# CircuitoEMitter.net
KiCad netlist of a schematic drawn in EAGLE
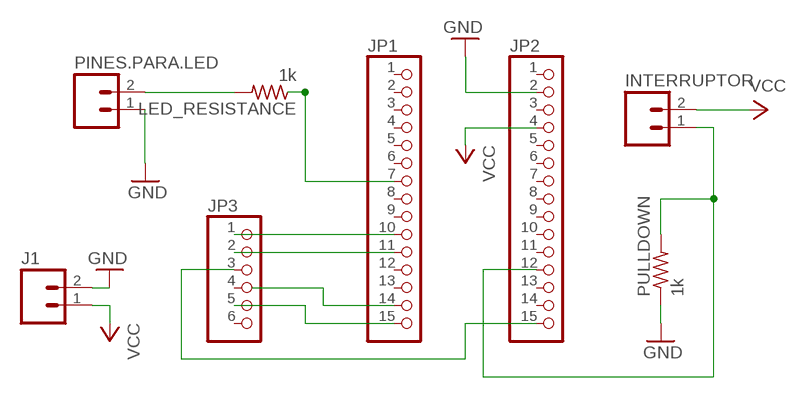
[diagram p0: schematic, sheet 1]

(export (version "E")
  (design (tool "Eeschema 10.0.6"))
  (components
    (comp (ref "INTERRUPTOR")
      (value "M02LOCK_LONGPADS")
      (footprint "eagle-import:1X02_LOCK_LONGPADS")
      (libsource (lib "eagle-import") (part "M02LOCK_LONGPADS"))
    )
    (comp (ref "J1")
      (value "M02POGO_PIN_HOLES_ONLY")
      (footprint "eagle-import:1X02_PP_HOLES_ONLY")
      (libsource (lib "eagle-import") (part "M02POGO_PIN_HOLES_ONLY"))
    )
    (comp (ref "JP1")
      (value "PINHD-1X15-CB")
      (footprint "eagle-import:1X15-CB")
      (libsource (lib "eagle-import") (part "PINHD-1X15-CB"))
    )
    (comp (ref "JP2")
      (value "PINHD-1X15-CB")
      (footprint "eagle-import:1X15-CB")
      (libsource (lib "eagle-import") (part "PINHD-1X15-CB"))
    )
    (comp (ref "JP3")
      (value "PINHD-1X6CLEAN")
      (footprint "eagle-import:1X06-CLEAN")
      (libsource (lib "eagle-import") (part "PINHD-1X6CLEAN"))
    )
    (comp (ref "LED_RESISTANCE")
      (value "1k")
      (footprint "eagle-import:0204_7")
      (libsource (lib "eagle-import") (part "R-US_0204/7"))
    )
    (comp (ref "PINES.PARA.LED")
      (value "M02LOCK_LONGPADS")
      (footprint "eagle-import:1X02_LOCK_LONGPADS")
      (libsource (lib "eagle-import") (part "M02LOCK_LONGPADS"))
    )
    (comp (ref "PULLDOWN")
      (value "1k")
      (footprint "eagle-import:0204_7")
      (libsource (lib "eagle-import") (part "R-US_0204/7"))
    )
  )
  (nets
    (net (code "1") (name "GND") (class "Default")
      (node (ref "J1") (pin "2") (pinfunction "2_2") (pintype "passive"))
      (node (ref "JP2") (pin "2") (pinfunction "2_2") (pintype "passive"))
      (node (ref "PINES.PARA.LED") (pin "1") (pinfunction "1_1") (pintype "passive"))
      (node (ref "PULLDOWN") (pin "1") (pinfunction "1_1") (pintype "passive"))
    )
    (net (code "2") (name "Net-(INTERRUPTOR-Pad1)") (class "Default")
      (node (ref "INTERRUPTOR") (pin "1") (pinfunction "1_1") (pintype "passive"))
      (node (ref "JP2") (pin "12") (pinfunction "12_12") (pintype "passive"))
      (node (ref "PULLDOWN") (pin "2") (pinfunction "2_2") (pintype "passive"))
    )
    (net (code "3") (name "Net-(JP1-Pad7)") (class "Default")
      (node (ref "JP1") (pin "7") (pinfunction "7_7") (pintype "passive"))
      (node (ref "LED_RESISTANCE") (pin "1") (pinfunction "1_1") (pintype "passive"))
    )
    (net (code "4") (name "Net-(JP1-Pad10)") (class "Default")
      (node (ref "JP1") (pin "10") (pinfunction "10_10") (pintype "passive"))
      (node (ref "JP3") (pin "1") (pinfunction "1_1") (pintype "passive"))
    )
    (net (code "5") (name "Net-(JP1-Pad11)") (class "Default")
      (node (ref "JP1") (pin "11") (pinfunction "11_11") (pintype "passive"))
      (node (ref "JP3") (pin "2") (pinfunction "2_2") (pintype "passive"))
    )
    (net (code "6") (name "Net-(JP1-Pad15)") (class "Default")
      (node (ref "JP1") (pin "15") (pinfunction "15_15") (pintype "passive"))
      (node (ref "JP3") (pin "5") (pinfunction "5_5") (pintype "passive"))
    )
    (net (code "7") (name "Net-(JP2-Pad15)") (class "Default")
      (node (ref "JP2") (pin "15") (pinfunction "15_15") (pintype "passive"))
      (node (ref "JP3") (pin "3") (pinfunction "3_3") (pintype "passive"))
    )
    (net (code "8") (name "Net-(LED_RESISTANCE-Pad2)") (class "Default")
      (node (ref "LED_RESISTANCE") (pin "2") (pinfunction "2_2") (pintype "passive"))
      (node (ref "PINES.PARA.LED") (pin "2") (pinfunction "2_2") (pintype "passive"))
    )
    (net (code "9") (name "VCC") (class "Default")
      (node (ref "INTERRUPTOR") (pin "2") (pinfunction "2_2") (pintype "passive"))
      (node (ref "J1") (pin "1") (pinfunction "1_1") (pintype "passive"))
      (node (ref "JP2") (pin "4") (pinfunction "4_4") (pintype "passive"))
    )
    (net (code "10") (name "unconnected-(JP1-Pad1)") (class "Default")
      (node (ref "JP1") (pin "1") (pinfunction "1_1") (pintype "passive"))
    )
    (net (code "11") (name "unconnected-(JP1-Pad2)") (class "Default")
      (node (ref "JP1") (pin "2") (pinfunction "2_2") (pintype "passive"))
    )
    (net (code "12") (name "unconnected-(JP1-Pad3)") (class "Default")
      (node (ref "JP1") (pin "3") (pinfunction "3_3") (pintype "passive"))
    )
    (net (code "13") (name "unconnected-(JP1-Pad4)") (class "Default")
      (node (ref "JP1") (pin "4") (pinfunction "4_4") (pintype "passive"))
    )
    (net (code "14") (name "unconnected-(JP1-Pad5)") (class "Default")
      (node (ref "JP1") (pin "5") (pinfunction "5_5") (pintype "passive"))
    )
    (net (code "15") (name "unconnected-(JP1-Pad6)") (class "Default")
      (node (ref "JP1") (pin "6") (pinfunction "6_6") (pintype "passive"))
    )
    (net (code "16") (name "unconnected-(JP1-Pad8)") (class "Default")
      (node (ref "JP1") (pin "8") (pinfunction "8_8") (pintype "passive"))
    )
    (net (code "17") (name "unconnected-(JP1-Pad9)") (class "Default")
      (node (ref "JP1") (pin "9") (pinfunction "9_9") (pintype "passive"))
    )
    (net (code "18") (name "unconnected-(JP1-Pad12)") (class "Default")
      (node (ref "JP1") (pin "12") (pinfunction "12_12") (pintype "passive"))
    )
    (net (code "19") (name "unconnected-(JP1-Pad13)") (class "Default")
      (node (ref "JP1") (pin "13") (pinfunction "13_13") (pintype "passive"))
    )
    (net (code "20") (name "unconnected-(JP1-Pad14)") (class "Default")
      (node (ref "JP1") (pin "14") (pinfunction "14_14") (pintype "passive"))
    )
    (net (code "21") (name "unconnected-(JP2-Pad1)") (class "Default")
      (node (ref "JP2") (pin "1") (pinfunction "1_1") (pintype "passive"))
    )
    (net (code "22") (name "unconnected-(JP2-Pad3)") (class "Default")
      (node (ref "JP2") (pin "3") (pinfunction "3_3") (pintype "passive"))
    )
    (net (code "23") (name "unconnected-(JP2-Pad5)") (class "Default")
      (node (ref "JP2") (pin "5") (pinfunction "5_5") (pintype "passive"))
    )
    (net (code "24") (name "unconnected-(JP2-Pad6)") (class "Default")
      (node (ref "JP2") (pin "6") (pinfunction "6_6") (pintype "passive"))
    )
    (net (code "25") (name "unconnected-(JP2-Pad7)") (class "Default")
      (node (ref "JP2") (pin "7") (pinfunction "7_7") (pintype "passive"))
    )
    (net (code "26") (name "unconnected-(JP2-Pad8)") (class "Default")
      (node (ref "JP2") (pin "8") (pinfunction "8_8") (pintype "passive"))
    )
    (net (code "27") (name "unconnected-(JP2-Pad9)") (class "Default")
      (node (ref "JP2") (pin "9") (pinfunction "9_9") (pintype "passive"))
    )
    (net (code "28") (name "unconnected-(JP2-Pad10)") (class "Default")
      (node (ref "JP2") (pin "10") (pinfunction "10_10") (pintype "passive"))
    )
    (net (code "29") (name "unconnected-(JP2-Pad11)") (class "Default")
      (node (ref "JP2") (pin "11") (pinfunction "11_11") (pintype "passive"))
    )
    (net (code "30") (name "unconnected-(JP2-Pad13)") (class "Default")
      (node (ref "JP2") (pin "13") (pinfunction "13_13") (pintype "passive"))
    )
    (net (code "31") (name "unconnected-(JP2-Pad14)") (class "Default")
      (node (ref "JP2") (pin "14") (pinfunction "14_14") (pintype "passive"))
    )
    (net (code "32") (name "unconnected-(JP3-Pad4)") (class "Default")
      (node (ref "JP3") (pin "4") (pinfunction "4_4") (pintype "passive"))
    )
    (net (code "33") (name "unconnected-(JP3-Pad6)") (class "Default")
      (node (ref "JP3") (pin "6") (pinfunction "6_6") (pintype "passive"))
    )
  )
)
